# 02_-_Power.net
KiCad netlist of a schematic drawn in Altium Designer
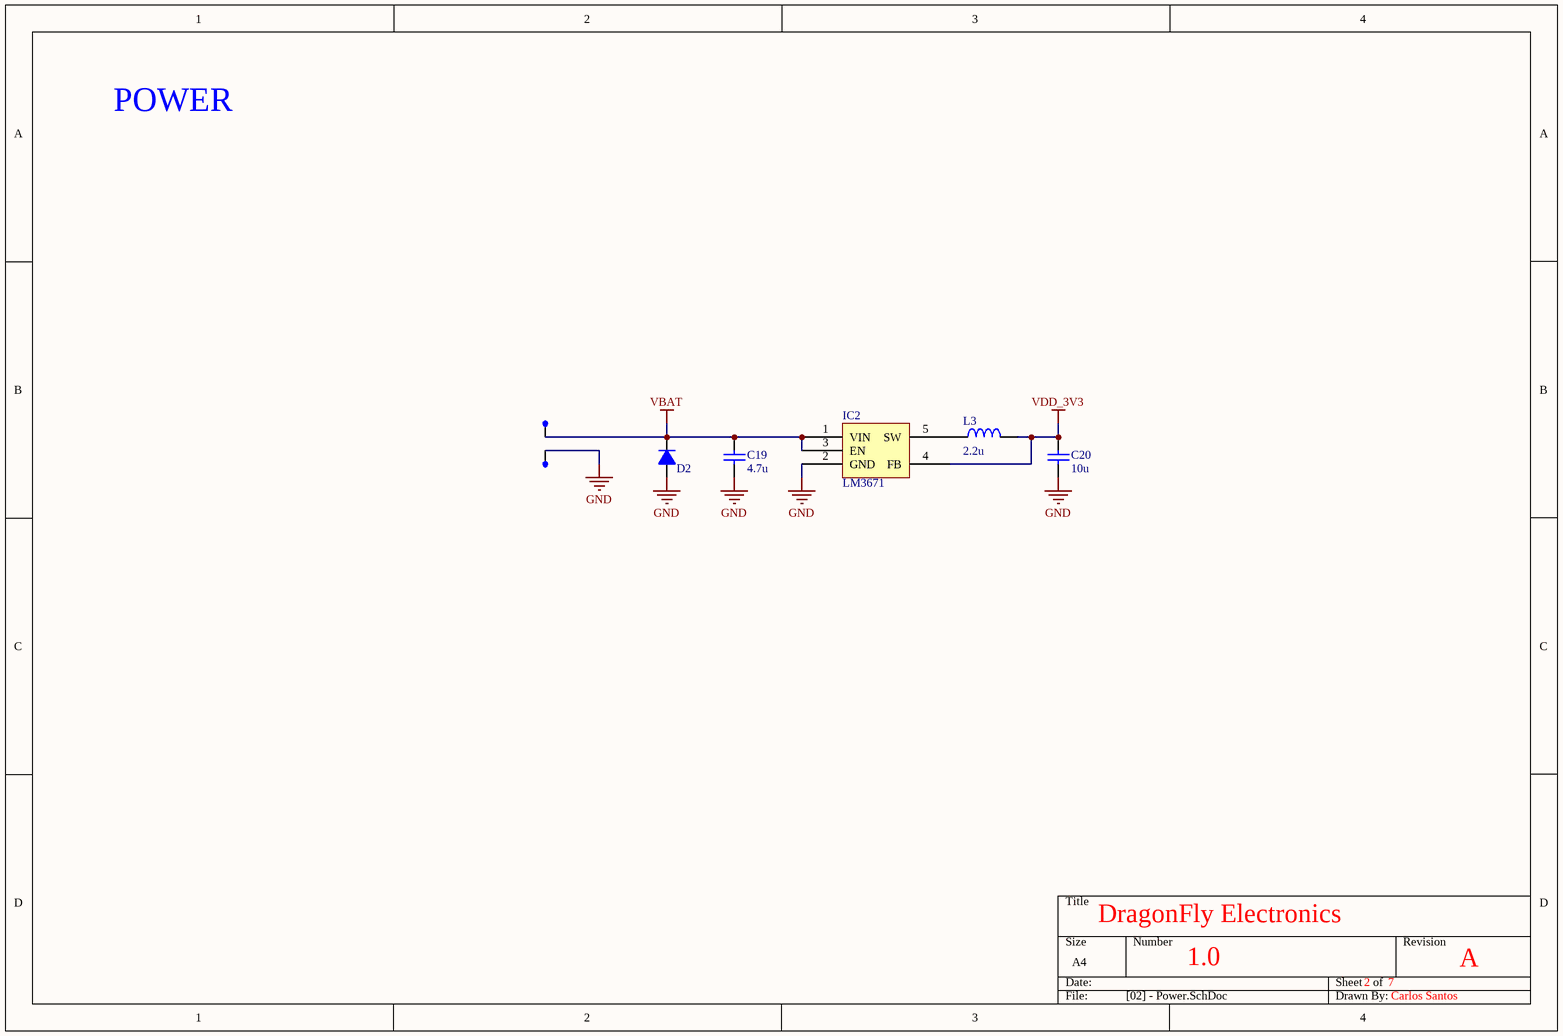
[diagram p0: [02] - Power.SchDoc]

(export (version "E")
  (design (tool "Eeschema 10.0.6"))
  (components
    (comp (ref "C19")
      (value "4.7u")
      (footprint "0402 - Capacitor")
      (fields (field (name "Comment") "Capacitor"))
      (libsource (lib "Mine") (part "Capacitor"))
    )
    (comp (ref "C20")
      (value "10u")
      (footprint "0603 - Capacitor")
      (fields (field (name "Comment") "Capacitor"))
      (libsource (lib "Mine") (part "Capacitor"))
    )
    (comp (ref "D2") (value "Diode") (footprint "SOD 923") (libsource (lib "Mine") (part "Diode")))
    (comp (ref "IC2")
      (value "LM3671")
      (footprint "SOT 23 - 5")
      (fields (field (name "DIGIKEY PART #") "LM3671MF-3.3/NOPBCT-ND"))
      (libsource (lib "Mine") (part "LM3671"))
    )
    (comp (ref "L3")
      (value "2.2u")
      (footprint "MDMK2020")
      (fields (field (name "Comment") "Inductor"))
      (libsource (lib "Mine") (part "Inductor"))
    )
    (comp (ref "SP15")
      (value "Signal Point")
      (footprint "Signal_point_1mm")
      (libsource (lib "Mine") (part "Signal Point"))
    )
    (comp (ref "SP16")
      (value "Signal Point")
      (footprint "Signal_point_1mm")
      (libsource (lib "Mine") (part "Signal Point"))
    )
  )
  (nets
    (net (code "1") (name "GND") (class "Default")
      (node (ref "C19") (pin "1") (pinfunction "1_1") (pintype "passive"))
      (node (ref "C20") (pin "1") (pinfunction "1_1") (pintype "passive"))
      (node (ref "D2") (pin "1") (pinfunction "A_1") (pintype "passive"))
      (node (ref "IC2") (pin "2") (pinfunction "GND_2") (pintype "passive"))
      (node (ref "SP16") (pin "0") (pinfunction "VIN_0") (pintype "passive"))
    )
    (net (code "2") (name "Net-(IC2-SW)") (class "Default")
      (node (ref "IC2") (pin "5") (pinfunction "SW_5") (pintype "passive"))
      (node (ref "L3") (pin "1") (pinfunction "1_1") (pintype "passive"))
    )
    (net (code "3") (name "VBAT") (class "Default")
      (node (ref "C19") (pin "2") (pinfunction "2_2") (pintype "passive"))
      (node (ref "D2") (pin "2") (pinfunction "K_2") (pintype "passive"))
      (node (ref "IC2") (pin "1") (pinfunction "VIN_1") (pintype "passive"))
      (node (ref "IC2") (pin "3") (pinfunction "EN_3") (pintype "passive"))
      (node (ref "SP15") (pin "0") (pinfunction "VIN_0") (pintype "passive"))
    )
    (net (code "4") (name "VDD_3V3") (class "Default")
      (node (ref "C20") (pin "2") (pinfunction "2_2") (pintype "passive"))
      (node (ref "IC2") (pin "4") (pinfunction "FB_4") (pintype "passive"))
      (node (ref "L3") (pin "2") (pinfunction "2_2") (pintype "passive"))
    )
  )
)
